# pOWER.net
KiCad netlist of a schematic drawn in Altium Designer
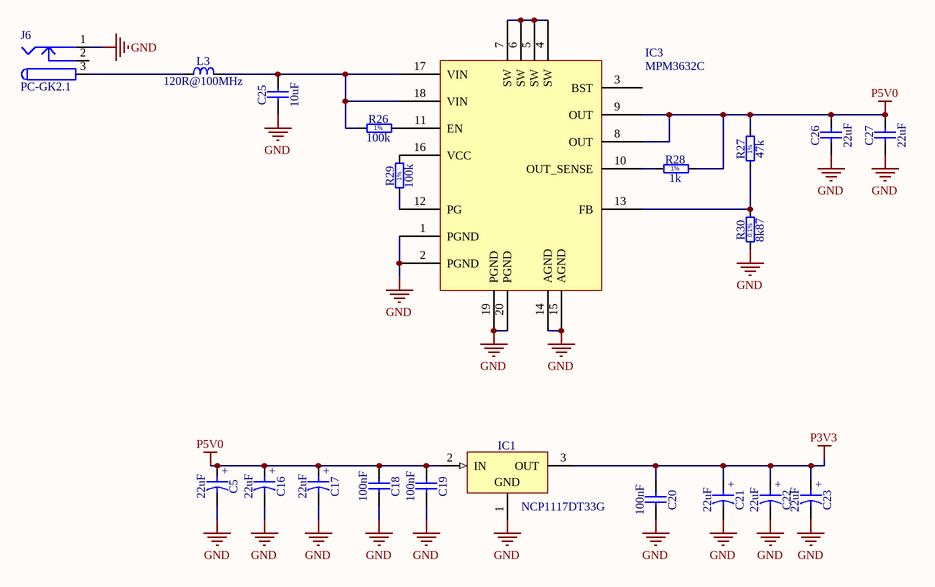
[diagram p0: pOWER.SchDoc]

(export (version "E")
  (design (tool "Eeschema 10.0.6"))
  (components
    (comp (ref "C5")
      (value "22uF")
      (footprint "CAPAE430X540N")
      (description "Polarised capacitor")
      (fields
        (field (name "PART NUMBER") "CAE430-540_22UF_10V_20%")
        (field (name "VOLTAGE") "10V")
        (field (name "AUTHOR") "CERN DEM JLC")
      )
      (libsource (lib "Capacitors") (part "Capacitor - polarized"))
    )
    (comp (ref "C16")
      (value "22uF")
      (footprint "CAPAE430X540N")
      (description "Polarised capacitor")
      (fields
        (field (name "PART NUMBER") "CAE430-540_22UF_10V_20%")
        (field (name "VOLTAGE") "10V")
        (field (name "AUTHOR") "CERN DEM JLC")
      )
      (libsource (lib "Capacitors") (part "Capacitor - polarized"))
    )
    (comp (ref "C17")
      (value "22uF")
      (footprint "CAPAE430X540N")
      (description "Polarised capacitor")
      (fields
        (field (name "PART NUMBER") "CAE430-540_22UF_10V_20%")
        (field (name "VOLTAGE") "10V")
        (field (name "AUTHOR") "CERN DEM JLC")
      )
      (libsource (lib "Capacitors") (part "Capacitor - polarized"))
    )
    (comp (ref "C18")
      (value "100nF")
      (footprint "CAPC1608X87N")
      (description "Non-polarised capacitor")
      (fields
        (field (name "PART NUMBER") "CC0603_100NF_50V_10%_X5R")
        (field (name "VOLTAGE") "50V")
        (field (name "AUTHOR") "CERN DEM MR")
      )
      (libsource (lib "Capacitors") (part "Capacitor - non polarized"))
    )
    (comp (ref "C19")
      (value "100nF")
      (footprint "CAPC1608X87N")
      (description "Non-polarised capacitor")
      (fields
        (field (name "PART NUMBER") "CC0603_100NF_50V_10%_X5R")
        (field (name "VOLTAGE") "50V")
        (field (name "AUTHOR") "CERN DEM MR")
      )
      (libsource (lib "Capacitors") (part "Capacitor - non polarized"))
    )
    (comp (ref "C20")
      (value "100nF")
      (footprint "CAPC1608X87N")
      (description "Non-polarised capacitor")
      (fields
        (field (name "PART NUMBER") "CC0603_100NF_50V_10%_X5R")
        (field (name "VOLTAGE") "50V")
        (field (name "AUTHOR") "CERN DEM MR")
      )
      (libsource (lib "Capacitors") (part "Capacitor - non polarized"))
    )
    (comp (ref "C21")
      (value "22uF")
      (footprint "CAPAE430X540N")
      (description "Polarised capacitor")
      (fields
        (field (name "PART NUMBER") "CAE430-540_22UF_10V_20%")
        (field (name "VOLTAGE") "10V")
        (field (name "AUTHOR") "CERN DEM JLC")
      )
      (libsource (lib "Capacitors") (part "Capacitor - polarized"))
    )
    (comp (ref "C22")
      (value "22uF")
      (footprint "CAPAE430X540N")
      (description "Polarised capacitor")
      (fields
        (field (name "PART NUMBER") "CAE430-540_22UF_10V_20%")
        (field (name "VOLTAGE") "10V")
        (field (name "AUTHOR") "CERN DEM JLC")
      )
      (libsource (lib "Capacitors") (part "Capacitor - polarized"))
    )
    (comp (ref "C23")
      (value "22uF")
      (footprint "CAPAE430X540N")
      (description "Polarised capacitor")
      (fields
        (field (name "PART NUMBER") "CAE430-540_22UF_10V_20%")
        (field (name "VOLTAGE") "10V")
        (field (name "AUTHOR") "CERN DEM JLC")
      )
      (libsource (lib "Capacitors") (part "Capacitor - polarized"))
    )
    (comp (ref "C25")
      (value "10uF")
      (footprint "CAPC2012X135N")
      (description "Non-polarised capacitor")
      (fields
        (field (name "PART NUMBER") "CC0805_10UF_16V_10%_X5R")
        (field (name "VOLTAGE") "16V")
        (field (name "AUTHOR") "CERN DEM JLC")
      )
      (libsource (lib "Capacitors") (part "Capacitor - non polarized"))
    )
    (comp (ref "C26")
      (value "22uF")
      (footprint "CAPC2012X135N")
      (description "Non-polarised capacitor")
      (fields
        (field (name "PART NUMBER") "CC0805_22UF_16V_10%_X5R")
        (field (name "VOLTAGE") "16V")
        (field (name "AUTHOR") "CERN DEM JLC")
      )
      (libsource (lib "Capacitors") (part "Capacitor - non polarized"))
    )
    (comp (ref "C27")
      (value "22uF")
      (footprint "CAPC2012X135N")
      (description "Non-polarised capacitor")
      (fields
        (field (name "PART NUMBER") "CC0805_22UF_16V_10%_X5R")
        (field (name "VOLTAGE") "16V")
        (field (name "AUTHOR") "CERN DEM JLC")
      )
      (libsource (lib "Capacitors") (part "Capacitor - non polarized"))
    )
    (comp (ref "IC1")
      (value "NCP1117DT33G")
      (footprint "TO228P991X239-3N-R552X520")
      (description "3-Terminal Regulator 1=GND 2=IN 3=OUT")
      (fields (field (name "MANUFACTURER") "ON SEMICONDUCTOR") (field (name "AUTHOR") "CERN DEM JLC"))
      (libsource (lib "ICs And Semiconductors") (part "REG3 1GND-2IN-3OUT"))
    )
    (comp (ref "IC3")
      (value "MPM3632C")
      (footprint "PCBComponent_1 - duplicate")
      (description "Power Management Module 18V 3A Step-Down Regulator Module")
      (fields
        (field (name "PART NUMBER") "MPM3632CG")
        (field (name "MANUFACTURER") "Monolithic Power Systems (MPS)")
      )
      (libsource (lib "MG_lib") (part "MPM3632C"))
    )
    (comp (ref "J6")
      (value "PC-GK2.1")
      (footprint "DC2020")
      (description "Power Barrel Connector Jack 2.1mm ID, 5.50mm OD,  Through Hole, Right Angle")
      (fields (field (name "MANUFACTURER") "NINIGI") (field (name "PUBLISHER") "Altium Limited"))
      (libsource (lib "LIBRARY_SCH") (part "CON_DC_JACK_TH"))
    )
    (comp (ref "L3")
      (value "120R@100MHz")
      (footprint "INDC1608X65N")
      (description "Ferrite Bead")
      (fields
        (field (name "PART NUMBER") "BLM18SG121TN1D")
        (field (name "POWER") "3A")
        (field (name "AUTHOR") "CERN DEM JLC")
      )
      (libsource (lib "Inductors & Transformers") (part "Inductor"))
    )
    (comp (ref "R26")
      (value "100k")
      (footprint "RESC1005X40N")
      (description "Resistor - 1%")
      (fields
        (field (name "PART NUMBER") "R0402_100K_1%_0.0625W_100PPM")
        (field (name "POWER") "0.0625W")
        (field (name "AUTHOR") "CERN DEM JLC")
      )
      (libsource (lib "Resistors") (part "Resistor - 1%"))
    )
    (comp (ref "R27")
      (value "47k")
      (footprint "RESC1005X40N")
      (description "Resistor - 1%")
      (fields
        (field (name "PART NUMBER") "R0402_47K_1%_0.0625W_100PPM")
        (field (name "POWER") "0.0625W")
        (field (name "AUTHOR") "CERN DEM JLC")
      )
      (libsource (lib "Resistors") (part "Resistor - 1%"))
    )
    (comp (ref "R28")
      (value "1k")
      (footprint "RESC1608X50N")
      (description "Resistor - 1%")
      (fields
        (field (name "PART NUMBER") "R0805_1K_1%_0.33W_100PPM_VISHAY_CRCW-HP")
        (field (name "POWER") "0.33W")
        (field (name "AUTHOR") "CERN DEM JLC")
      )
      (libsource (lib "Resistors") (part "Resistor - 1%"))
    )
    (comp (ref "R29")
      (value "100k")
      (footprint "RESC1005X40N")
      (description "Resistor - 1%")
      (fields
        (field (name "PART NUMBER") "R0402_100K_1%_0.0625W_100PPM")
        (field (name "POWER") "0.0625W")
        (field (name "AUTHOR") "CERN DEM JLC")
      )
      (libsource (lib "Resistors") (part "Resistor - 1%"))
    )
    (comp (ref "R30")
      (value "8k87")
      (footprint "RESC1608X55N")
      (description "Resistor - 0.1%")
      (fields
        (field (name "PART NUMBER") "R0603_8K87_0.1%_0.063W_10PPM")
        (field (name "POWER") "0.063W")
        (field (name "AUTHOR") "CERN DEM JLC")
      )
      (libsource (lib "Resistors") (part "Resistor - 0.1%"))
    )
  )
  (nets
    (net (code "1") (name "GND") (class "Default")
      (node (ref "C16") (pin "2") (pinfunction "2_2") (pintype "passive"))
      (node (ref "C17") (pin "2") (pinfunction "2_2") (pintype "passive"))
      (node (ref "C18") (pin "2") (pinfunction "2_2") (pintype "passive"))
      (node (ref "C19") (pin "2") (pinfunction "2_2") (pintype "passive"))
      (node (ref "C20") (pin "2") (pinfunction "2_2") (pintype "passive"))
      (node (ref "C21") (pin "2") (pinfunction "2_2") (pintype "passive"))
      (node (ref "C22") (pin "2") (pinfunction "2_2") (pintype "passive"))
      (node (ref "C23") (pin "2") (pinfunction "2_2") (pintype "passive"))
      (node (ref "C25") (pin "1") (pinfunction "1_1") (pintype "passive"))
      (node (ref "C26") (pin "1") (pinfunction "1_1") (pintype "passive"))
      (node (ref "C27") (pin "1") (pinfunction "1_1") (pintype "passive"))
      (node (ref "C5") (pin "2") (pinfunction "2_2") (pintype "passive"))
      (node (ref "IC1") (pin "1") (pinfunction "GND_1") (pintype "power_in"))
      (node (ref "IC3") (pin "1") (pinfunction "PGND_1") (pintype "power_in"))
      (node (ref "IC3") (pin "14") (pinfunction "AGND_14") (pintype "power_in"))
      (node (ref "IC3") (pin "15") (pinfunction "AGND_15") (pintype "power_in"))
      (node (ref "IC3") (pin "19") (pinfunction "PGND_19") (pintype "power_in"))
      (node (ref "IC3") (pin "2") (pinfunction "PGND_2") (pintype "power_in"))
      (node (ref "IC3") (pin "20") (pinfunction "PGND_20") (pintype "power_in"))
      (node (ref "J6") (pin "1") (pintype "power_in"))
      (node (ref "R30") (pin "1") (pinfunction "1_1") (pintype "passive"))
    )
    (net (code "2") (name "Net-(C25-Pad2)") (class "Default")
      (node (ref "C25") (pin "2") (pinfunction "2_2") (pintype "passive"))
      (node (ref "IC3") (pin "17") (pinfunction "VIN_17") (pintype "power_in"))
      (node (ref "IC3") (pin "18") (pinfunction "VIN_18") (pintype "power_in"))
      (node (ref "L3") (pin "2") (pinfunction "2_2") (pintype "passive"))
      (node (ref "R26") (pin "1") (pinfunction "1_1") (pintype "passive"))
    )
    (net (code "3") (name "Net-(IC3-EN)") (class "Default")
      (node (ref "IC3") (pin "11") (pinfunction "EN_11") (pintype "power_in"))
      (node (ref "R26") (pin "2") (pinfunction "2_2") (pintype "passive"))
    )
    (net (code "4") (name "Net-(IC3-FB)") (class "Default")
      (node (ref "IC3") (pin "13") (pinfunction "FB_13") (pintype "power_in"))
      (node (ref "R27") (pin "1") (pinfunction "1_1") (pintype "passive"))
      (node (ref "R30") (pin "2") (pinfunction "2_2") (pintype "passive"))
    )
    (net (code "5") (name "Net-(IC3-OUT_SENSE)") (class "Default")
      (node (ref "IC3") (pin "10") (pinfunction "OUT_SENSE_10") (pintype "power_in"))
      (node (ref "R28") (pin "1") (pinfunction "1_1") (pintype "passive"))
    )
    (net (code "6") (name "Net-(IC3-PG)") (class "Default")
      (node (ref "IC3") (pin "12") (pinfunction "PG_12") (pintype "power_in"))
      (node (ref "R29") (pin "1") (pinfunction "1_1") (pintype "passive"))
    )
    (net (code "7") (name "Net-(IC3-SW-Pad4)") (class "Default")
      (node (ref "IC3") (pin "4") (pinfunction "SW_4") (pintype "power_in"))
      (node (ref "IC3") (pin "5") (pinfunction "SW_5") (pintype "power_in"))
      (node (ref "IC3") (pin "6") (pinfunction "SW_6") (pintype "power_in"))
      (node (ref "IC3") (pin "7") (pinfunction "SW_7") (pintype "power_in"))
    )
    (net (code "8") (name "Net-(IC3-VCC)") (class "Default")
      (node (ref "IC3") (pin "16") (pinfunction "VCC_16") (pintype "power_in"))
      (node (ref "R29") (pin "2") (pinfunction "2_2") (pintype "passive"))
    )
    (net (code "9") (name "Net-(J6-Pad3)") (class "Default")
      (node (ref "J6") (pin "3") (pintype "power_in"))
      (node (ref "L3") (pin "1") (pinfunction "1_1") (pintype "passive"))
    )
    (net (code "10") (name "P3V3") (class "Default")
      (node (ref "C20") (pin "1") (pinfunction "1_1") (pintype "passive"))
      (node (ref "C21") (pin "1") (pinfunction "1_1") (pintype "passive"))
      (node (ref "C22") (pin "1") (pinfunction "1_1") (pintype "passive"))
      (node (ref "C23") (pin "1") (pinfunction "1_1") (pintype "passive"))
      (node (ref "IC1") (pin "3") (pinfunction "OUT_3") (pintype "power_in"))
    )
    (net (code "11") (name "P5V0") (class "Default")
      (node (ref "C16") (pin "1") (pinfunction "1_1") (pintype "passive"))
      (node (ref "C17") (pin "1") (pinfunction "1_1") (pintype "passive"))
      (node (ref "C18") (pin "1") (pinfunction "1_1") (pintype "passive"))
      (node (ref "C19") (pin "1") (pinfunction "1_1") (pintype "passive"))
      (node (ref "C26") (pin "2") (pinfunction "2_2") (pintype "passive"))
      (node (ref "C27") (pin "2") (pinfunction "2_2") (pintype "passive"))
      (node (ref "C5") (pin "1") (pinfunction "1_1") (pintype "passive"))
      (node (ref "IC1") (pin "2") (pinfunction "IN_2") (pintype "input"))
      (node (ref "IC3") (pin "8") (pinfunction "OUT_8") (pintype "power_in"))
      (node (ref "IC3") (pin "9") (pinfunction "OUT_9") (pintype "power_in"))
      (node (ref "R27") (pin "2") (pinfunction "2_2") (pintype "passive"))
      (node (ref "R28") (pin "2") (pinfunction "2_2") (pintype "passive"))
    )
    (net (code "12") (name "unconnected-(IC3-BST-Pad3)") (class "Default")
      (node (ref "IC3") (pin "3") (pinfunction "BST_3") (pintype "power_in"))
    )
    (net (code "13") (name "unconnected-(J6-Pad2)") (class "Default")
      (node (ref "J6") (pin "2") (pintype "power_in"))
    )
  )
)
